# Adafruit_MPR121Q_QT.net
KiCad netlist of a schematic drawn in EAGLE
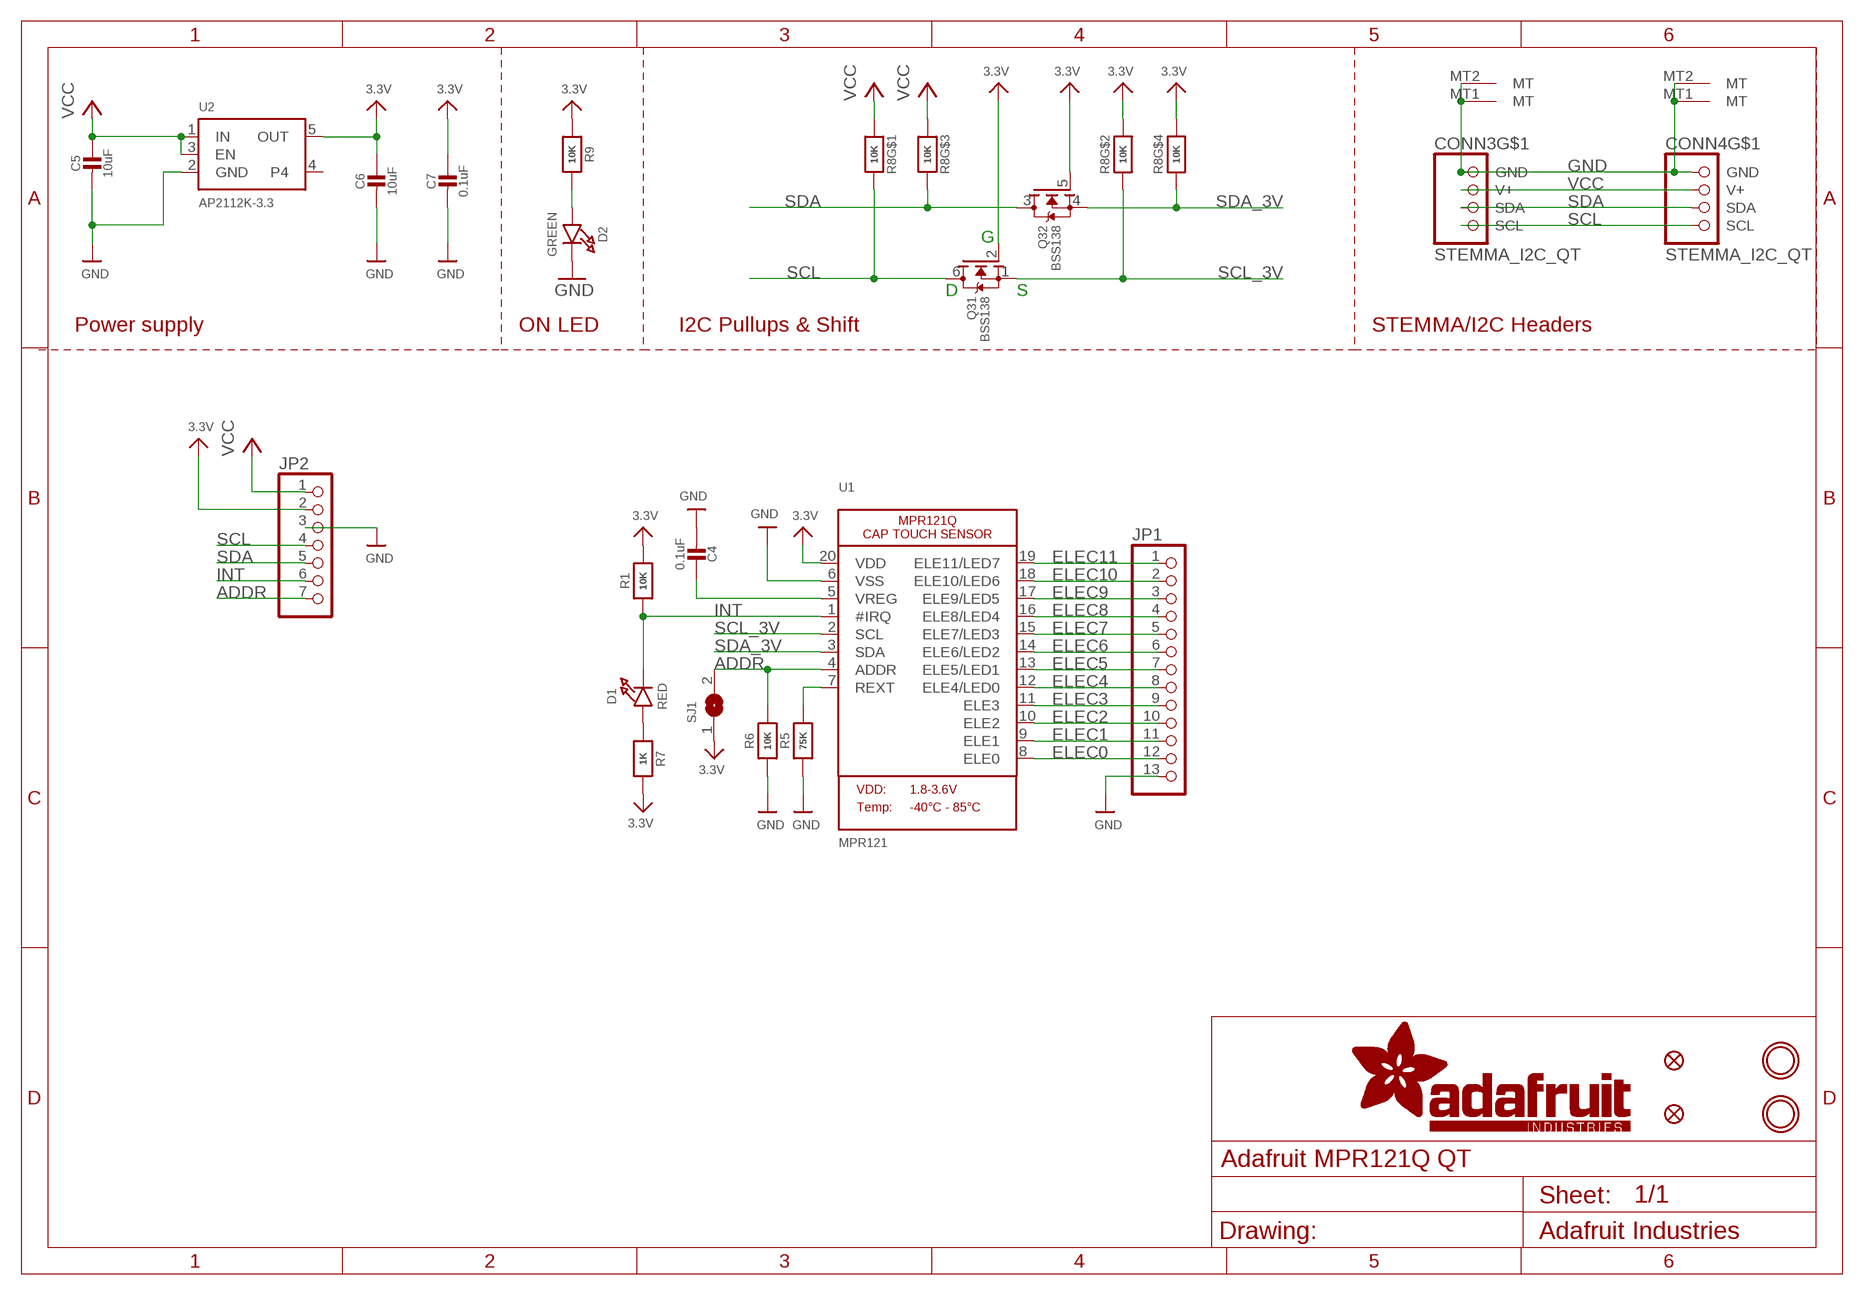
[diagram p0: schematic, sheet 1]

(export (version "E")
  (design (tool "Eeschema 10.0.6"))
  (components
    (comp (ref "C4")
      (value "0.1uF")
      (footprint "eagle-import:0603-NO")
      (libsource (lib "eagle-import") (part "CAP_CERAMIC0603_NO"))
    )
    (comp (ref "C5")
      (value "10uF")
      (footprint "eagle-import:0805-NO")
      (libsource (lib "eagle-import") (part "CAP_CERAMIC0805-NOOUTLINE"))
    )
    (comp (ref "C6")
      (value "10uF")
      (footprint "eagle-import:0805-NO")
      (libsource (lib "eagle-import") (part "CAP_CERAMIC0805-NOOUTLINE"))
    )
    (comp (ref "C7")
      (value "0.1uF")
      (footprint "eagle-import:0603-NO")
      (libsource (lib "eagle-import") (part "CAP_CERAMIC0603_NO"))
    )
    (comp (ref "CONN3")
      (value "STEMMA_I2C_QT")
      (footprint "eagle-import:JST_SH4")
      (libsource (lib "eagle-import") (part "STEMMA_I2C_QT"))
    )
    (comp (ref "CONN4")
      (value "STEMMA_I2C_QT")
      (footprint "eagle-import:JST_SH4")
      (libsource (lib "eagle-import") (part "STEMMA_I2C_QT"))
    )
    (comp (ref "D1")
      (value "RED")
      (footprint "eagle-import:CHIPLED_0603_NOOUTLINE")
      (libsource (lib "eagle-import") (part "LED0603_NOOUTLINE"))
    )
    (comp (ref "D2")
      (value "GREEN")
      (footprint "eagle-import:CHIPLED_0603_NOOUTLINE")
      (libsource (lib "eagle-import") (part "LED0603_NOOUTLINE"))
    )
    (comp (ref "FID3")
      (value "FIDUCIAL_1MM")
      (footprint "eagle-import:FIDUCIAL_1MM")
      (libsource (lib "eagle-import") (part "FIDUCIAL_1MM"))
    )
    (comp (ref "FID4")
      (value "FIDUCIAL_1MM")
      (footprint "eagle-import:FIDUCIAL_1MM")
      (libsource (lib "eagle-import") (part "FIDUCIAL_1MM"))
    )
    (comp (ref "JP1")
      (value "HEADER-1X13")
      (footprint "eagle-import:1X13_ROUND_70")
      (libsource (lib "eagle-import") (part "HEADER-1X13"))
    )
    (comp (ref "JP2")
      (value "HEADER-1X770MIL")
      (footprint "eagle-import:1X07_ROUND_70")
      (libsource (lib "eagle-import") (part "HEADER-1X770MIL"))
    )
    (comp (ref "Q3")
      (value "BSS138")
      (footprint "eagle-import:SOT363")
      (libsource (lib "eagle-import") (part "MOSFET-N_DUAL"))
    )
    (comp (ref "R1")
      (value "10K")
      (footprint "eagle-import:0603-NO")
      (libsource (lib "eagle-import") (part "RESISTOR_0603_NOOUT"))
    )
    (comp (ref "R5")
      (value "75K")
      (footprint "eagle-import:0603-NO")
      (libsource (lib "eagle-import") (part "RESISTOR_0603_NOOUT"))
    )
    (comp (ref "R6")
      (value "10K")
      (footprint "eagle-import:0603-NO")
      (libsource (lib "eagle-import") (part "RESISTOR_0603_NOOUT"))
    )
    (comp (ref "R7")
      (value "1K")
      (footprint "eagle-import:0603-NO")
      (fields (field (name "REV") "E"))
      (libsource (lib "eagle-import") (part "RESISTOR_0603_NOOUT"))
    )
    (comp (ref "R8")
      (value "10K")
      (footprint "eagle-import:RESPACK_4X0603")
      (libsource (lib "eagle-import") (part "RESISTOR_4PACK"))
    )
    (comp (ref "R9")
      (value "10K")
      (footprint "eagle-import:0603-NO")
      (libsource (lib "eagle-import") (part "RESISTOR_0603_NOOUT"))
    )
    (comp (ref "SJ1")
      (value "SOLDERJUMPER")
      (footprint "eagle-import:SOLDERJUMPER_ARROW_NOPASTE")
      (libsource (lib "eagle-import") (part "SOLDERJUMPER"))
    )
    (comp (ref "U$34")
      (value "MOUNTINGHOLE2.5")
      (footprint "eagle-import:MOUNTINGHOLE_2.5_PLATED")
      (libsource (lib "eagle-import") (part "MOUNTINGHOLE2.5"))
    )
    (comp (ref "U$35")
      (value "MOUNTINGHOLE2.5")
      (footprint "eagle-import:MOUNTINGHOLE_2.5_PLATED")
      (libsource (lib "eagle-import") (part "MOUNTINGHOLE2.5"))
    )
    (comp (ref "U1")
      (value "MPR121")
      (footprint "eagle-import:QFN20_3MM_NOTHERMAL")
      (libsource (lib "eagle-import") (part "MPR121Q"))
    )
    (comp (ref "U2")
      (value "AP2112K-3.3")
      (footprint "eagle-import:SOT23-5")
      (libsource (lib "eagle-import") (part "VREG_SOT23-5"))
    )
  )
  (nets
    (net (code "1") (name "/ADDR") (class "Default")
      (node (ref "JP2") (pin "7") (pinfunction "7_7") (pintype "passive"))
      (node (ref "R6") (pin "2") (pinfunction "2_2") (pintype "passive"))
      (node (ref "SJ1") (pin "2") (pinfunction "2_2") (pintype "passive"))
      (node (ref "U1") (pin "4") (pinfunction "ADDR_4") (pintype "bidirectional"))
    )
    (net (code "2") (name "/ELEC0") (class "Default")
      (node (ref "JP1") (pin "12") (pinfunction "12_12") (pintype "passive"))
      (node (ref "U1") (pin "8") (pinfunction "ELE0_8") (pintype "bidirectional"))
    )
    (net (code "3") (name "/ELEC1") (class "Default")
      (node (ref "JP1") (pin "11") (pinfunction "11_11") (pintype "passive"))
      (node (ref "U1") (pin "9") (pinfunction "ELE1_9") (pintype "bidirectional"))
    )
    (net (code "4") (name "/ELEC2") (class "Default")
      (node (ref "JP1") (pin "10") (pinfunction "10_10") (pintype "passive"))
      (node (ref "U1") (pin "10") (pinfunction "ELE2_10") (pintype "bidirectional"))
    )
    (net (code "5") (name "/ELEC3") (class "Default")
      (node (ref "JP1") (pin "9") (pinfunction "9_9") (pintype "passive"))
      (node (ref "U1") (pin "11") (pinfunction "ELE3_11") (pintype "bidirectional"))
    )
    (net (code "6") (name "/ELEC4") (class "Default")
      (node (ref "JP1") (pin "8") (pinfunction "8_8") (pintype "passive"))
      (node (ref "U1") (pin "12") (pinfunction "ELE4/LED0_12") (pintype "bidirectional"))
    )
    (net (code "7") (name "/ELEC5") (class "Default")
      (node (ref "JP1") (pin "7") (pinfunction "7_7") (pintype "passive"))
      (node (ref "U1") (pin "13") (pinfunction "ELE5/LED1_13") (pintype "bidirectional"))
    )
    (net (code "8") (name "/ELEC6") (class "Default")
      (node (ref "JP1") (pin "6") (pinfunction "6_6") (pintype "passive"))
      (node (ref "U1") (pin "14") (pinfunction "ELE6/LED2_14") (pintype "bidirectional"))
    )
    (net (code "9") (name "/ELEC7") (class "Default")
      (node (ref "JP1") (pin "5") (pinfunction "5_5") (pintype "passive"))
      (node (ref "U1") (pin "15") (pinfunction "ELE7/LED3_15") (pintype "bidirectional"))
    )
    (net (code "10") (name "/ELEC8") (class "Default")
      (node (ref "JP1") (pin "4") (pinfunction "4_4") (pintype "passive"))
      (node (ref "U1") (pin "16") (pinfunction "ELE8/LED4_16") (pintype "bidirectional"))
    )
    (net (code "11") (name "/ELEC9") (class "Default")
      (node (ref "JP1") (pin "3") (pinfunction "3_3") (pintype "passive"))
      (node (ref "U1") (pin "17") (pinfunction "ELE9/LED5_17") (pintype "bidirectional"))
    )
    (net (code "12") (name "/ELEC10") (class "Default")
      (node (ref "JP1") (pin "2") (pinfunction "2_2") (pintype "passive"))
      (node (ref "U1") (pin "18") (pinfunction "ELE10/LED6_18") (pintype "bidirectional"))
    )
    (net (code "13") (name "/ELEC11") (class "Default")
      (node (ref "JP1") (pin "1") (pinfunction "1_1") (pintype "passive"))
      (node (ref "U1") (pin "19") (pinfunction "ELE11/LED7_19") (pintype "bidirectional"))
    )
    (net (code "14") (name "/INT") (class "Default")
      (node (ref "D1") (pin "C") (pinfunction "C_C") (pintype "passive"))
      (node (ref "JP2") (pin "6") (pinfunction "6_6") (pintype "passive"))
      (node (ref "R1") (pin "1") (pinfunction "1_1") (pintype "passive"))
      (node (ref "U1") (pin "1") (pinfunction "#IRQ_1") (pintype "bidirectional"))
    )
    (net (code "15") (name "/SCL") (class "Default")
      (node (ref "CONN3") (pin "4") (pinfunction "SCL_4") (pintype "passive"))
      (node (ref "CONN4") (pin "4") (pinfunction "SCL_4") (pintype "passive"))
      (node (ref "JP2") (pin "4") (pinfunction "4_4") (pintype "passive"))
      (node (ref "Q3") (pin "6") (pinfunction "D_6") (pintype "bidirectional"))
      (node (ref "R8") (pin "8") (pinfunction "2_8") (pintype "passive"))
    )
    (net (code "16") (name "/SCL_3V") (class "Default")
      (node (ref "Q3") (pin "1") (pinfunction "S_1") (pintype "bidirectional"))
      (node (ref "R8") (pin "7") (pinfunction "2_7") (pintype "passive"))
      (node (ref "U1") (pin "2") (pinfunction "SCL_2") (pintype "bidirectional"))
    )
    (net (code "17") (name "/SDA") (class "Default")
      (node (ref "CONN3") (pin "3") (pinfunction "SDA_3") (pintype "passive"))
      (node (ref "CONN4") (pin "3") (pinfunction "SDA_3") (pintype "passive"))
      (node (ref "JP2") (pin "5") (pinfunction "5_5") (pintype "passive"))
      (node (ref "Q3") (pin "3") (pinfunction "D_3") (pintype "bidirectional"))
      (node (ref "R8") (pin "6") (pinfunction "2_6") (pintype "passive"))
    )
    (net (code "18") (name "/SDA_3V") (class "Default")
      (node (ref "Q3") (pin "4") (pinfunction "S_4") (pintype "bidirectional"))
      (node (ref "R8") (pin "5") (pinfunction "2_5") (pintype "passive"))
      (node (ref "U1") (pin "3") (pinfunction "SDA_3") (pintype "bidirectional"))
    )
    (net (code "19") (name "3.3V") (class "Default")
      (node (ref "C6") (pin "1") (pinfunction "1_1") (pintype "passive"))
      (node (ref "C7") (pin "1") (pinfunction "1_1") (pintype "passive"))
      (node (ref "JP2") (pin "2") (pinfunction "2_2") (pintype "passive"))
      (node (ref "Q3") (pin "2") (pinfunction "G_2") (pintype "bidirectional"))
      (node (ref "Q3") (pin "5") (pinfunction "G_5") (pintype "bidirectional"))
      (node (ref "R1") (pin "2") (pinfunction "2_2") (pintype "passive"))
      (node (ref "R7") (pin "2") (pinfunction "2_2") (pintype "passive"))
      (node (ref "R8") (pin "2") (pinfunction "1_2") (pintype "passive"))
      (node (ref "R8") (pin "4") (pinfunction "1_4") (pintype "passive"))
      (node (ref "R9") (pin "1") (pinfunction "1_1") (pintype "passive"))
      (node (ref "SJ1") (pin "1") (pinfunction "1_1") (pintype "passive"))
      (node (ref "U1") (pin "20") (pinfunction "VDD_20") (pintype "power_in"))
      (node (ref "U2") (pin "5") (pinfunction "OUT_5") (pintype "power_in"))
    )
    (net (code "20") (name "GND") (class "Default")
      (node (ref "C4") (pin "2") (pinfunction "2_2") (pintype "passive"))
      (node (ref "C5") (pin "2") (pinfunction "2_2") (pintype "passive"))
      (node (ref "C6") (pin "2") (pinfunction "2_2") (pintype "passive"))
      (node (ref "C7") (pin "2") (pinfunction "2_2") (pintype "passive"))
      (node (ref "CONN3") (pin "1") (pinfunction "GND_1") (pintype "passive"))
      (node (ref "CONN3") (pin "MT1") (pinfunction "MT_MT1") (pintype "bidirectional"))
      (node (ref "CONN3") (pin "MT2") (pinfunction "MT_MT2") (pintype "bidirectional"))
      (node (ref "CONN4") (pin "1") (pinfunction "GND_1") (pintype "passive"))
      (node (ref "CONN4") (pin "MT1") (pinfunction "MT_MT1") (pintype "bidirectional"))
      (node (ref "CONN4") (pin "MT2") (pinfunction "MT_MT2") (pintype "bidirectional"))
      (node (ref "D2") (pin "C") (pinfunction "C_C") (pintype "passive"))
      (node (ref "JP1") (pin "13") (pinfunction "13_13") (pintype "passive"))
      (node (ref "JP2") (pin "3") (pinfunction "3_3") (pintype "passive"))
      (node (ref "R5") (pin "1") (pinfunction "1_1") (pintype "passive"))
      (node (ref "R6") (pin "1") (pinfunction "1_1") (pintype "passive"))
      (node (ref "U1") (pin "6") (pinfunction "VSS_6") (pintype "power_in"))
      (node (ref "U2") (pin "2") (pinfunction "GND_2") (pintype "power_in"))
    )
    (net (code "21") (name "Net-(D1-PadA)") (class "Default")
      (node (ref "D1") (pin "A") (pinfunction "A_A") (pintype "passive"))
      (node (ref "R7") (pin "1") (pinfunction "1_1") (pintype "passive"))
    )
    (net (code "22") (name "Net-(D2-PadA)") (class "Default")
      (node (ref "D2") (pin "A") (pinfunction "A_A") (pintype "passive"))
      (node (ref "R9") (pin "2") (pinfunction "2_2") (pintype "passive"))
    )
    (net (code "23") (name "Net-(U1-REXT)") (class "Default")
      (node (ref "R5") (pin "2") (pinfunction "2_2") (pintype "passive"))
      (node (ref "U1") (pin "7") (pinfunction "REXT_7") (pintype "bidirectional"))
    )
    (net (code "24") (name "Net-(U1-VREG)") (class "Default")
      (node (ref "C4") (pin "1") (pinfunction "1_1") (pintype "passive"))
      (node (ref "U1") (pin "5") (pinfunction "VREG_5") (pintype "bidirectional"))
    )
    (net (code "25") (name "VCC") (class "Default")
      (node (ref "C5") (pin "1") (pinfunction "1_1") (pintype "passive"))
      (node (ref "CONN3") (pin "2") (pinfunction "V+_2") (pintype "passive"))
      (node (ref "CONN4") (pin "2") (pinfunction "V+_2") (pintype "passive"))
      (node (ref "JP2") (pin "1") (pinfunction "1_1") (pintype "passive"))
      (node (ref "R8") (pin "1") (pinfunction "1_1") (pintype "passive"))
      (node (ref "R8") (pin "3") (pinfunction "1_3") (pintype "passive"))
      (node (ref "U2") (pin "1") (pinfunction "IN_1") (pintype "power_in"))
      (node (ref "U2") (pin "3") (pinfunction "EN_3") (pintype "input"))
    )
    (net (code "26") (name "unconnected-(U2-P4-Pad4)") (class "Default")
      (node (ref "U2") (pin "4") (pinfunction "P4_4") (pintype "bidirectional"))
    )
  )
)
